# ESP232_USB_C_SCH_1.net
KiCad netlist of a schematic drawn in Altium Designer
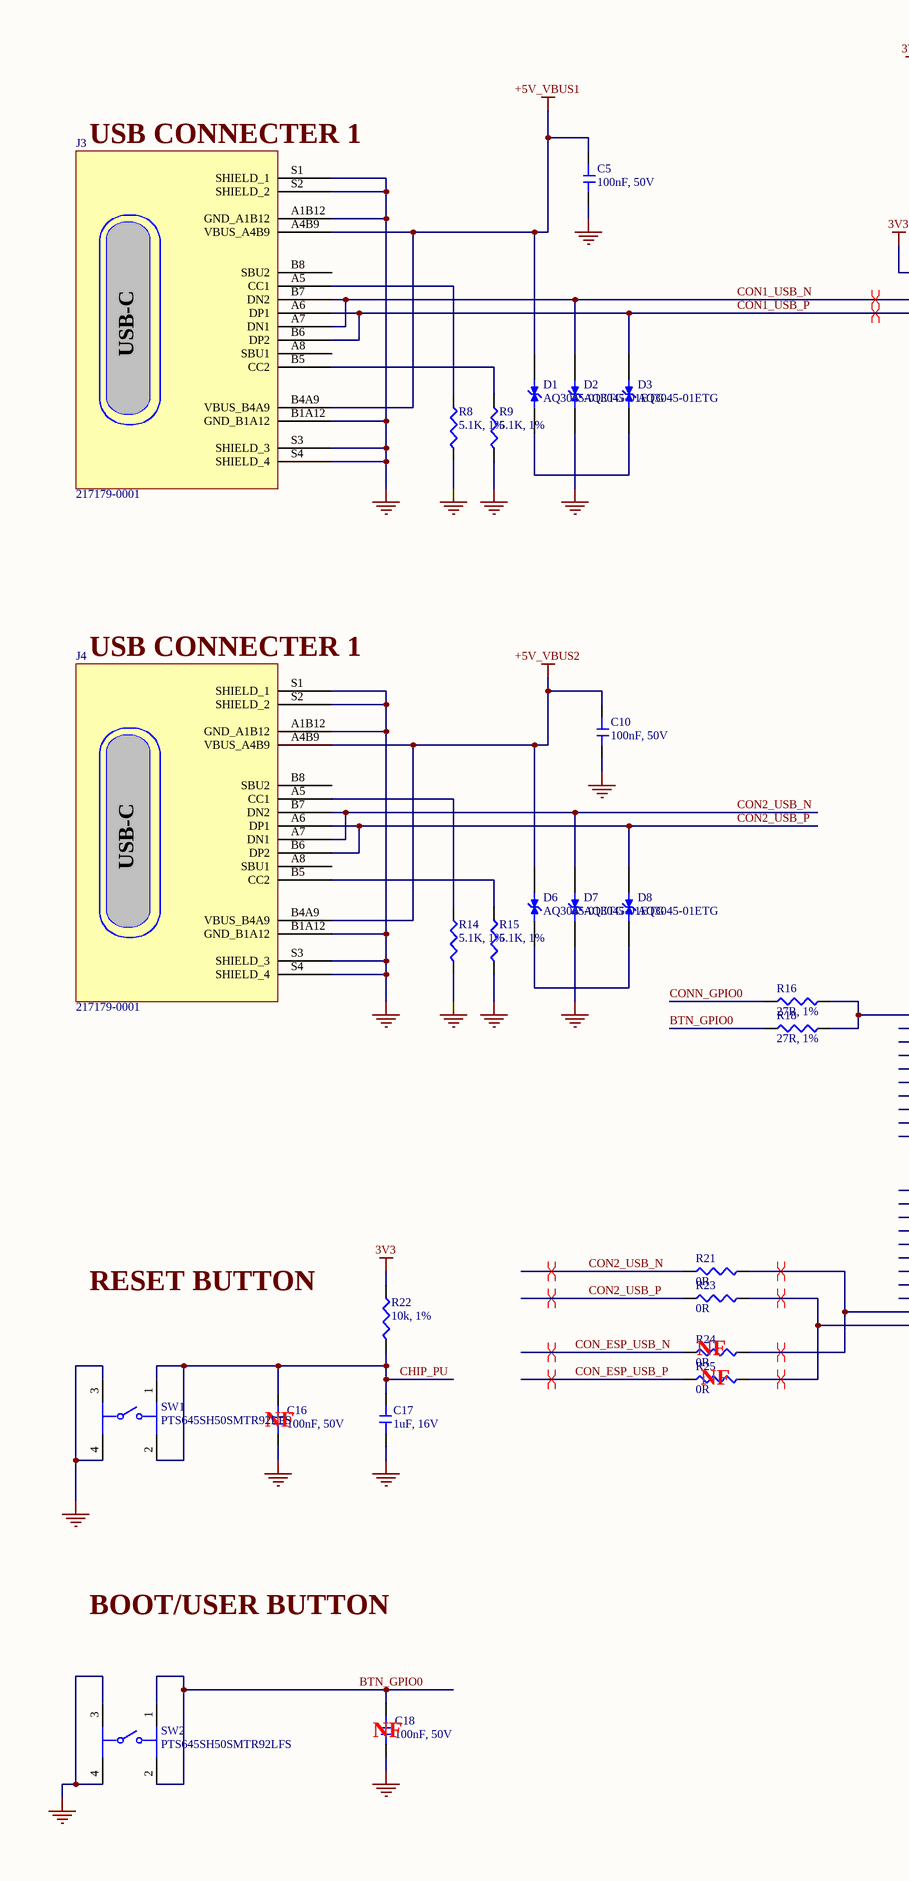
[diagram p0: ESP232_USB_C_SCH_1.SchDoc, left]
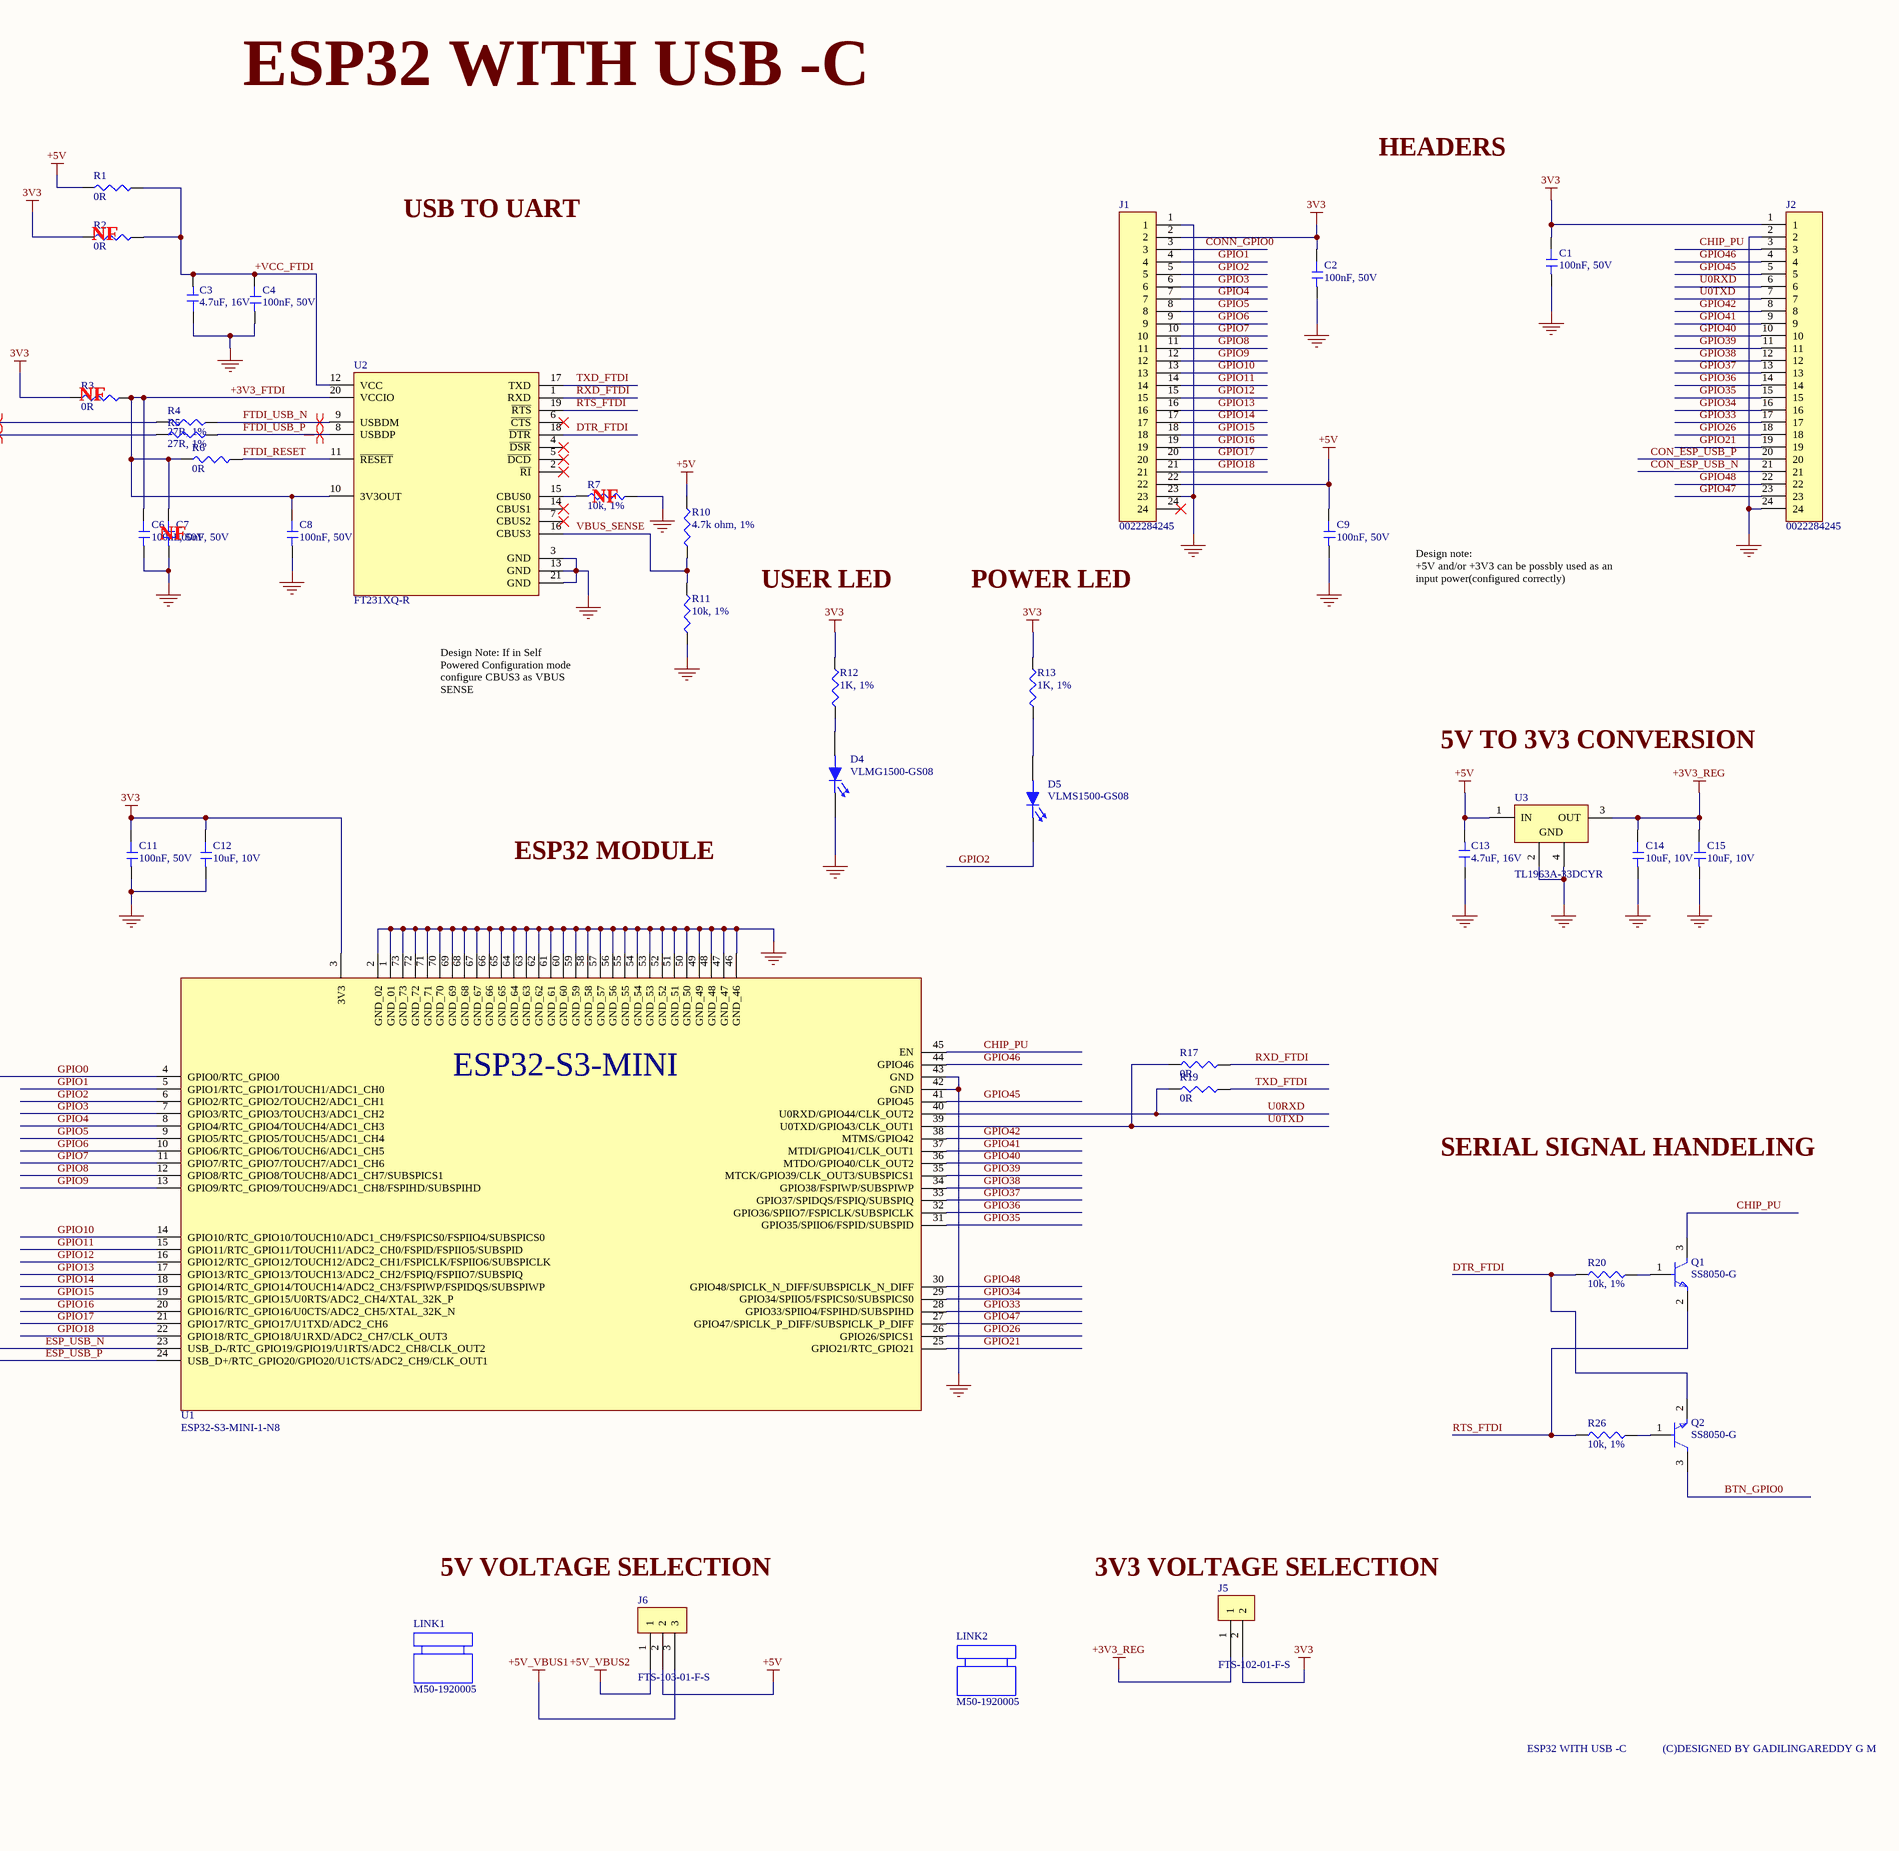
[diagram p1: ESP232_USB_C_SCH_1.SchDoc, right]

(export (version "E")
  (design (tool "Eeschema 10.0.6"))
  (components
    (comp (ref "C1")
      (value "100nF, 50V")
      (footprint "CAPC1005X55N")
      (description "CAP CER 0.1UF 50V X7R 0402")
      (fields
        (field (name "MANUFACTURER") "Samsung")
        (field (name "MANUFACTURER PART NUMBER") "CL05B104KB54PNC")
      )
      (libsource (lib "Schlib1") (part "CL05B104KB54PNC"))
    )
    (comp (ref "C2")
      (value "100nF, 50V")
      (footprint "CAPC1005X55N")
      (description "CAP CER 0.1UF 50V X7R 0402")
      (fields
        (field (name "MANUFACTURER") "Samsung")
        (field (name "MANUFACTURER PART NUMBER") "CL05B104KB54PNC")
      )
      (libsource (lib "Schlib1") (part "CL05B104KB54PNC"))
    )
    (comp (ref "C3")
      (value "4.7uF, 16V")
      (footprint "CAPC1005X55N")
      (description "CAP CER 4.7UF 16V X5R 0402")
      (fields
        (field (name "MANUFACTURER") "Samsung")
        (field (name "MANUFACTURER PART NUMBER") "CL05A475MO5NUNC")
      )
      (libsource (lib "Schlib1") (part "CL05A475MO5NUNC"))
    )
    (comp (ref "C4")
      (value "100nF, 50V")
      (footprint "CAPC1005X55N")
      (description "CAP CER 0.1UF 50V X7R 0402")
      (fields
        (field (name "MANUFACTURER") "Samsung")
        (field (name "MANUFACTURER PART NUMBER") "CL05B104KB54PNC")
      )
      (libsource (lib "Schlib1") (part "CL05B104KB54PNC"))
    )
    (comp (ref "C5")
      (value "100nF, 50V")
      (footprint "CAPC1005X55N")
      (description "CAP CER 0.1UF 50V X7R 0402")
      (fields
        (field (name "MANUFACTURER") "Samsung")
        (field (name "MANUFACTURER PART NUMBER") "CL05B104KB54PNC")
      )
      (libsource (lib "Schlib1") (part "CL05B104KB54PNC"))
    )
    (comp (ref "C6")
      (value "100nF, 50V")
      (footprint "CAPC1005X55N")
      (description "CAP CER 0.1UF 50V X7R 0402")
      (fields
        (field (name "MANUFACTURER") "Samsung")
        (field (name "MANUFACTURER PART NUMBER") "CL05B104KB54PNC")
      )
      (libsource (lib "Schlib1") (part "CL05B104KB54PNC"))
    )
    (comp (ref "C7")
      (value "100nF, 50V")
      (footprint "CAPC1005X55N")
      (description "CAP CER 0.1UF 50V X7R 0402")
      (fields
        (field (name "MANUFACTURER") "Samsung")
        (field (name "MANUFACTURER PART NUMBER") "CL05B104KB54PNC")
      )
      (libsource (lib "Schlib1") (part "CL05B104KB54PNC"))
    )
    (comp (ref "C8")
      (value "100nF, 50V")
      (footprint "CAPC1005X55N")
      (description "CAP CER 0.1UF 50V X7R 0402")
      (fields
        (field (name "MANUFACTURER") "Samsung")
        (field (name "MANUFACTURER PART NUMBER") "CL05B104KB54PNC")
      )
      (libsource (lib "Schlib1") (part "CL05B104KB54PNC"))
    )
    (comp (ref "C9")
      (value "100nF, 50V")
      (footprint "CAPC1005X55N")
      (description "CAP CER 0.1UF 50V X7R 0402")
      (fields
        (field (name "MANUFACTURER") "Samsung")
        (field (name "MANUFACTURER PART NUMBER") "CL05B104KB54PNC")
      )
      (libsource (lib "Schlib1") (part "CL05B104KB54PNC"))
    )
    (comp (ref "C10")
      (value "100nF, 50V")
      (footprint "CAPC1005X55N")
      (description "CAP CER 0.1UF 50V X7R 0402")
      (fields
        (field (name "MANUFACTURER") "Samsung")
        (field (name "MANUFACTURER PART NUMBER") "CL05B104KB54PNC")
      )
      (libsource (lib "Schlib1") (part "CL05B104KB54PNC"))
    )
    (comp (ref "C11")
      (value "100nF, 50V")
      (footprint "CAPC1005X55N")
      (description "CAP CER 0.1UF 50V X7R 0402")
      (fields
        (field (name "MANUFACTURER") "Samsung")
        (field (name "MANUFACTURER PART NUMBER") "CL05B104KB54PNC")
      )
      (libsource (lib "Schlib1") (part "CL05B104KB54PNC"))
    )
    (comp (ref "C12")
      (value "10uF, 10V")
      (footprint "CAPC1005X55N")
      (description "CAP CER 10UF 10V X5R 0402")
      (fields
        (field (name "MANUFACTURER") "Samsung")
        (field (name "MANUFACTURER PART NUMBER") "CL05A106MP8NUB8")
      )
      (libsource (lib "Schlib1") (part "CL05A106MP8NUB8"))
    )
    (comp (ref "C13")
      (value "4.7uF, 16V")
      (footprint "CAPC1005X55N")
      (description "CAP CER 4.7UF 16V X5R 0402")
      (fields
        (field (name "MANUFACTURER") "Samsung")
        (field (name "MANUFACTURER PART NUMBER") "CL05A475MO5NUNC")
      )
      (libsource (lib "Schlib1") (part "CL05A475MO5NUNC"))
    )
    (comp (ref "C14")
      (value "10uF, 10V")
      (footprint "CAPC1005X55N")
      (description "CAP CER 10UF 10V X5R 0402")
      (fields
        (field (name "MANUFACTURER") "Samsung")
        (field (name "MANUFACTURER PART NUMBER") "CL05A106MP8NUB8")
      )
      (libsource (lib "Schlib1") (part "CL05A106MP8NUB8"))
    )
    (comp (ref "C15")
      (value "10uF, 10V")
      (footprint "CAPC1005X55N")
      (description "CAP CER 10UF 10V X5R 0402")
      (fields
        (field (name "MANUFACTURER") "Samsung")
        (field (name "MANUFACTURER PART NUMBER") "CL05A106MP8NUB8")
      )
      (libsource (lib "Schlib1") (part "CL05A106MP8NUB8"))
    )
    (comp (ref "C16")
      (value "100nF, 50V")
      (footprint "CAPC1005X55N")
      (description "CAP CER 0.1UF 50V X7R 0402")
      (fields
        (field (name "MANUFACTURER") "Samsung")
        (field (name "MANUFACTURER PART NUMBER") "CL05B104KB54PNC")
      )
      (libsource (lib "Schlib1") (part "CL05B104KB54PNC"))
    )
    (comp (ref "C17")
      (value "1uF, 16V")
      (footprint "CAPC1005X55N")
      (description "CAP CER 1UF 16V X5R 0402")
      (fields
        (field (name "MANUFACTURER") "Samsung")
        (field (name "MANUFACTURER PART NUMBER") "CL05A105KO5NNNC")
      )
      (libsource (lib "Schlib1") (part "CL05A105KO5NNNC"))
    )
    (comp (ref "C18")
      (value "100nF, 50V")
      (footprint "CAPC1005X55N")
      (description "CAP CER 0.1UF 50V X7R 0402")
      (fields
        (field (name "MANUFACTURER") "Samsung")
        (field (name "MANUFACTURER PART NUMBER") "CL05B104KB54PNC")
      )
      (libsource (lib "Schlib1") (part "CL05B104KB54PNC"))
    )
    (comp (ref "D1")
      (value "AQ3045-01ETG")
      (footprint "ESD_TVS_DIODE")
      (description "TVS DIODE 5.3VWM 12VC SOD882")
      (fields (field (name "MANUFACTURER") "Littelfuse") (field (name "LCSC PART NUMBER") "C3710326"))
      (libsource (lib "Schlib1") (part "AQ3045-01ETG"))
    )
    (comp (ref "D2")
      (value "AQ3045-01ETG")
      (footprint "ESD_TVS_DIODE")
      (description "TVS DIODE 5.3VWM 12VC SOD882")
      (fields (field (name "MANUFACTURER") "Littelfuse") (field (name "LCSC PART NUMBER") "C3710326"))
      (libsource (lib "Schlib1") (part "AQ3045-01ETG"))
    )
    (comp (ref "D3")
      (value "AQ3045-01ETG")
      (footprint "ESD_TVS_DIODE")
      (description "TVS DIODE 5.3VWM 12VC SOD882")
      (fields (field (name "MANUFACTURER") "Littelfuse") (field (name "LCSC PART NUMBER") "C3710326"))
      (libsource (lib "Schlib1") (part "AQ3045-01ETG"))
    )
    (comp (ref "D4")
      (value "VLMG1500-GS08")
      (footprint "GREEN_LED")
      (description "LED YLW-GRN 0402 SMD")
      (fields (field (name "MANUFACTURER") "Vishay") (field (name "LCSC PART NUMBER") "C511404"))
      (libsource (lib "Schlib1") (part "VLMG1500-GS08"))
    )
    (comp (ref "D5")
      (value "VLMS1500-GS08")
      (footprint "RED_LED")
      (description "LED RED 0402 SMD")
      (fields (field (name "MANUFACTURER") "Vishay") (field (name "LCSC PART NUMBER") "C511370"))
      (libsource (lib "Schlib1_1") (part "VLMS1500-GS08"))
    )
    (comp (ref "D6")
      (value "AQ3045-01ETG")
      (footprint "ESD_TVS_DIODE")
      (description "TVS DIODE 5.3VWM 12VC SOD882")
      (fields (field (name "MANUFACTURER") "Littelfuse") (field (name "LCSC PART NUMBER") "C3710326"))
      (libsource (lib "Schlib1") (part "AQ3045-01ETG"))
    )
    (comp (ref "D7")
      (value "AQ3045-01ETG")
      (footprint "ESD_TVS_DIODE")
      (description "TVS DIODE 5.3VWM 12VC SOD882")
      (fields (field (name "MANUFACTURER") "Littelfuse") (field (name "LCSC PART NUMBER") "C3710326"))
      (libsource (lib "Schlib1") (part "AQ3045-01ETG"))
    )
    (comp (ref "D8")
      (value "AQ3045-01ETG")
      (footprint "ESD_TVS_DIODE")
      (description "TVS DIODE 5.3VWM 12VC SOD882")
      (fields (field (name "MANUFACTURER") "Littelfuse") (field (name "LCSC PART NUMBER") "C3710326"))
      (libsource (lib "Schlib1") (part "AQ3045-01ETG"))
    )
    (comp (ref "J1")
      (value "0022284245")
      (footprint "HDR_1X24_2.54MM - duplicate")
      (description "CONN HEADER VERT 24POS 2.54MM")
      (fields (field (name "MANUFACTURER") "Molex") (field (name "LCSC PART NUMBER") "C7145888"))
      (libsource (lib "Schlib1") (part "0022284245"))
    )
    (comp (ref "J2")
      (value "0022284245")
      (footprint "HDR_1X24_2.54MM - duplicate")
      (description "CONN HEADER VERT 24POS 2.54MM")
      (fields (field (name "MANUFACTURER") "Molex") (field (name "LCSC PART NUMBER") "C7145888"))
      (libsource (lib "") (part "0022284245_1"))
    )
    (comp (ref "J3")
      (value "217179-0001")
      (footprint "FP-2171790001-MFG")
      (description "CONN RCP USB2.0 TYP C 24P SMD RA")
      (fields (field (name "MANUFACTURER") "Molex") (field (name "LCSC PART NUMBER") "C2894899"))
      (libsource (lib "Schlib1") (part "217179-0001"))
    )
    (comp (ref "J4")
      (value "217179-0001")
      (footprint "FP-2171790001-MFG")
      (description "CONN RCP USB2.0 TYP C 24P SMD RA")
      (fields (field (name "MANUFACTURER") "Molex") (field (name "LCSC PART NUMBER") "C2894899"))
      (libsource (lib "Schlib1") (part "217179-0001"))
    )
    (comp (ref "J5")
      (value "FTS-102-01-F-S")
      (footprint "HDR_1X2_1.27MM")
      (description "CONN HEADER VERT 2POS 1.27MM")
      (fields (field (name "MANUFACTURER") "Samtec") (field (name "LCSC PART NUMBER") "C6045317"))
      (libsource (lib "Schlib1") (part "FTS-102-01-F-S"))
    )
    (comp (ref "J6")
      (value "FTS-103-01-F-S")
      (footprint "HDR_1X3_1.27MM")
      (description "CONN HEADER VERT 3POS 1.27MM")
      (fields (field (name "MANUFACTURER") "Samtec") (field (name "LCSC PART NUMBER") "C3333578"))
      (libsource (lib "Schlib1") (part "FTS-103-01-F-S"))
    )
    (comp (ref "LINK1")
      (value "M50-1920005")
      (description "CONN SHUNT 1.27MM RED")
      (fields (field (name "MANUFACTURER") "Harwin") (field (name "LCSC PART NUMBER") "C6985646"))
      (libsource (lib "Schlib1") (part "M50-1920005"))
    )
    (comp (ref "LINK2")
      (value "M50-1920005")
      (description "CONN SHUNT 1.27MM RED")
      (fields (field (name "MANUFACTURER") "Harwin") (field (name "LCSC PART NUMBER") "C6985646"))
      (libsource (lib "Schlib1") (part "M50-1920005"))
    )
    (comp (ref "Q1")
      (value "SS8050-G")
      (footprint "FP-SS8050-G-IPC_B")
      (description "TRANS NPN 25V 1.5A SOT23-3")
      (fields (field (name "MANUFACTURER") "Comchip") (field (name "LCSC PART NUMBER") "C164885"))
      (libsource (lib "Schlib1") (part "SS8050-G"))
    )
    (comp (ref "Q2")
      (value "SS8050-G")
      (footprint "FP-SS8050-G-IPC_B")
      (description "TRANS NPN 25V 1.5A SOT23-3")
      (fields (field (name "MANUFACTURER") "Comchip") (field (name "LCSC PART NUMBER") "C164885"))
      (libsource (lib "Schlib1") (part "SS8050-G"))
    )
    (comp (ref "R1")
      (value "0R")
      (footprint "RESC1005X37N")
      (description "RES 0 OHM JUMPER 1/16W 0402")
      (fields
        (field (name "MANUFACTURER") "Yageo")
        (field (name "MANUFACTURER PART NUMBER") "RC0402JR-070RL")
      )
      (libsource (lib "Schlib1") (part "RC0402JR-070RL"))
    )
    (comp (ref "R2")
      (value "0R")
      (footprint "RESC1005X37N")
      (description "RES 0 OHM JUMPER 1/16W 0402")
      (fields
        (field (name "MANUFACTURER") "Yageo")
        (field (name "MANUFACTURER PART NUMBER") "RC0402JR-070RL")
      )
      (libsource (lib "Schlib1") (part "RC0402JR-070RL"))
    )
    (comp (ref "R3")
      (value "0R")
      (footprint "RESC1005X37N")
      (description "RES 0 OHM JUMPER 1/16W 0402")
      (fields
        (field (name "MANUFACTURER") "Yageo")
        (field (name "MANUFACTURER PART NUMBER") "RC0402JR-070RL")
      )
      (libsource (lib "Schlib1") (part "RC0402JR-070RL"))
    )
    (comp (ref "R4")
      (value "27R, 1%")
      (footprint "RESC1005X37N")
      (description "RES 27 OHM 1% 1/16W 0402")
      (fields
        (field (name "MANUFACTURER") "Yageo")
        (field (name "MANUFACTURER PART NUMBER") "RC0402FR-0727RL")
      )
      (libsource (lib "Schlib1") (part "RC0402FR-0727RL"))
    )
    (comp (ref "R5")
      (value "27R, 1%")
      (footprint "RESC1005X37N")
      (description "RES 27 OHM 1% 1/16W 0402")
      (fields
        (field (name "MANUFACTURER") "Yageo")
        (field (name "MANUFACTURER PART NUMBER") "RC0402FR-0727RL")
      )
      (libsource (lib "Schlib1") (part "RC0402FR-0727RL"))
    )
    (comp (ref "R6")
      (value "0R")
      (footprint "RESC1005X37N")
      (description "RES 0 OHM JUMPER 1/16W 0402")
      (fields
        (field (name "MANUFACTURER") "Yageo")
        (field (name "MANUFACTURER PART NUMBER") "RC0402JR-070RL")
      )
      (libsource (lib "Schlib1") (part "RC0402JR-070RL"))
    )
    (comp (ref "R7")
      (value "10k, 1%")
      (footprint "RESC1005X37N")
      (description "RES 10K OHM 1% 1/16W 0402")
      (fields
        (field (name "MANUFACTURER") "Yageo")
        (field (name "MANUFACTURER PART NUMBER") "RC0402FR-0710KL")
      )
      (libsource (lib "Schlib1") (part "RC0402FR-0710KL"))
    )
    (comp (ref "R8")
      (value "5.1K, 1%")
      (footprint "RESC1005X37N")
      (description "RES SMD 5.1K OHM 1% 1/16W 0402")
      (fields
        (field (name "MANUFACTURER") "Yageo")
        (field (name "MANUFACTURER PART NUMBER") "AF0402FR-075K1L")
      )
      (libsource (lib "Schlib1") (part "AF0402FR-075K1L"))
    )
    (comp (ref "R9")
      (value "5.1K, 1%")
      (footprint "RESC1005X37N")
      (description "RES SMD 5.1K OHM 1% 1/16W 0402")
      (fields
        (field (name "MANUFACTURER") "Yageo")
        (field (name "MANUFACTURER PART NUMBER") "AF0402FR-075K1L")
      )
      (libsource (lib "Schlib1") (part "AF0402FR-075K1L"))
    )
    (comp (ref "R10")
      (value "4.7k ohm, 1%")
      (footprint "RESC1005X37N")
      (description "RES 4.7K OHM 1% 1/16W 0402")
      (fields
        (field (name "MANUFACTURER") "Yageo")
        (field (name "MANUFACTURER PART NUMBER") "RC0402FR-074K7L")
      )
      (libsource (lib "Schlib1") (part "RC0402FR-074K7L"))
    )
    (comp (ref "R11")
      (value "10k, 1%")
      (footprint "RESC1005X37N")
      (description "RES 10K OHM 1% 1/16W 0402")
      (fields
        (field (name "MANUFACTURER") "Yageo")
        (field (name "MANUFACTURER PART NUMBER") "RC0402FR-0710KL")
      )
      (libsource (lib "Schlib1") (part "RC0402FR-0710KL"))
    )
    (comp (ref "R12")
      (value "1K, 1%")
      (footprint "RESC1005X37N")
      (description "RES 1K OHM 1% 1/32W 01005")
      (fields
        (field (name "MANUFACTURER") "Yageo")
        (field (name "MANUFACTURER PART NUMBER") "RC0100FR-071KL")
      )
      (libsource (lib "Schlib1") (part "RC0100FR-071KL"))
    )
    (comp (ref "R13")
      (value "1K, 1%")
      (footprint "RESC1005X37N")
      (description "RES 1K OHM 1% 1/32W 01005")
      (fields
        (field (name "MANUFACTURER") "Yageo")
        (field (name "MANUFACTURER PART NUMBER") "RC0100FR-071KL")
      )
      (libsource (lib "Schlib1") (part "RC0100FR-071KL"))
    )
    (comp (ref "R14")
      (value "5.1K, 1%")
      (footprint "RESC1005X37N")
      (description "RES SMD 5.1K OHM 1% 1/16W 0402")
      (fields
        (field (name "MANUFACTURER") "Yageo")
        (field (name "MANUFACTURER PART NUMBER") "AF0402FR-075K1L")
      )
      (libsource (lib "Schlib1") (part "AF0402FR-075K1L"))
    )
    (comp (ref "R15")
      (value "5.1K, 1%")
      (footprint "RESC1005X37N")
      (description "RES SMD 5.1K OHM 1% 1/16W 0402")
      (fields
        (field (name "MANUFACTURER") "Yageo")
        (field (name "MANUFACTURER PART NUMBER") "AF0402FR-075K1L")
      )
      (libsource (lib "Schlib1") (part "AF0402FR-075K1L"))
    )
    (comp (ref "R16")
      (value "27R, 1%")
      (footprint "RESC1005X37N")
      (description "RES 27 OHM 1% 1/16W 0402")
      (fields
        (field (name "MANUFACTURER") "Yageo")
        (field (name "MANUFACTURER PART NUMBER") "RC0402FR-0727RL")
      )
      (libsource (lib "Schlib1") (part "RC0402FR-0727RL"))
    )
    (comp (ref "R17")
      (value "0R")
      (footprint "RESC1005X37N")
      (description "RES 0 OHM JUMPER 1/16W 0402")
      (fields
        (field (name "MANUFACTURER") "Yageo")
        (field (name "MANUFACTURER PART NUMBER") "RC0402JR-070RL")
      )
      (libsource (lib "Schlib1") (part "RC0402JR-070RL"))
    )
    (comp (ref "R18")
      (value "27R, 1%")
      (footprint "RESC1005X37N")
      (description "RES 27 OHM 1% 1/16W 0402")
      (fields
        (field (name "MANUFACTURER") "Yageo")
        (field (name "MANUFACTURER PART NUMBER") "RC0402FR-0727RL")
      )
      (libsource (lib "Schlib1") (part "RC0402FR-0727RL"))
    )
    (comp (ref "R19")
      (value "0R")
      (footprint "RESC1005X37N")
      (description "RES 0 OHM JUMPER 1/16W 0402")
      (fields
        (field (name "MANUFACTURER") "Yageo")
        (field (name "MANUFACTURER PART NUMBER") "RC0402JR-070RL")
      )
      (libsource (lib "Schlib1") (part "RC0402JR-070RL"))
    )
    (comp (ref "R20")
      (value "10k, 1%")
      (footprint "RESC1005X37N")
      (description "RES 10K OHM 1% 1/16W 0402")
      (fields
        (field (name "MANUFACTURER") "Yageo")
        (field (name "MANUFACTURER PART NUMBER") "RC0402FR-0710KL")
      )
      (libsource (lib "Schlib1") (part "RC0402FR-0710KL"))
    )
    (comp (ref "R21")
      (value "0R")
      (footprint "RESC1005X37N")
      (description "RES 0 OHM JUMPER 1/16W 0402")
      (fields
        (field (name "MANUFACTURER") "Yageo")
        (field (name "MANUFACTURER PART NUMBER") "RC0402JR-070RL")
      )
      (libsource (lib "Schlib1") (part "RC0402JR-070RL"))
    )
    (comp (ref "R22")
      (value "10k, 1%")
      (footprint "RESC1005X37N")
      (description "RES 10K OHM 1% 1/16W 0402")
      (fields
        (field (name "MANUFACTURER") "Yageo")
        (field (name "MANUFACTURER PART NUMBER") "RC0402FR-0710KL")
      )
      (libsource (lib "Schlib1") (part "RC0402FR-0710KL"))
    )
    (comp (ref "R23")
      (value "0R")
      (footprint "RESC1005X37N")
      (description "RES 0 OHM JUMPER 1/16W 0402")
      (fields
        (field (name "MANUFACTURER") "Yageo")
        (field (name "MANUFACTURER PART NUMBER") "RC0402JR-070RL")
      )
      (libsource (lib "Schlib1") (part "RC0402JR-070RL"))
    )
    (comp (ref "R24")
      (value "0R")
      (footprint "RESC1005X37N")
      (description "RES 0 OHM JUMPER 1/16W 0402")
      (fields
        (field (name "MANUFACTURER") "Yageo")
        (field (name "MANUFACTURER PART NUMBER") "RC0402JR-070RL")
      )
      (libsource (lib "Schlib1") (part "RC0402JR-070RL"))
    )
    (comp (ref "R25")
      (value "0R")
      (footprint "RESC1005X37N")
      (description "RES 0 OHM JUMPER 1/16W 0402")
      (fields
        (field (name "MANUFACTURER") "Yageo")
        (field (name "MANUFACTURER PART NUMBER") "RC0402JR-070RL")
      )
      (libsource (lib "Schlib1") (part "RC0402JR-070RL"))
    )
    (comp (ref "R26")
      (value "10k, 1%")
      (footprint "RESC1005X37N")
      (description "RES 10K OHM 1% 1/16W 0402")
      (fields
        (field (name "MANUFACTURER") "Yageo")
        (field (name "MANUFACTURER PART NUMBER") "RC0402FR-0710KL")
      )
      (libsource (lib "Schlib1") (part "RC0402FR-0710KL"))
    )
    (comp (ref "SW1")
      (value "PTS645SH50SMTR92LFS")
      (footprint "FP-PTS645SH50SMTR92LFS-MFG")
      (description "SWITCH TACTILE SPST-NO 0.05A 12V")
      (fields (field (name "MANUFACTURER") "ITT C&K") (field (name "LCSC PART NUMBER") "C221869"))
      (libsource (lib "Schlib1") (part "PTS645SH50SMTR92LFS"))
    )
    (comp (ref "SW2")
      (value "PTS645SH50SMTR92LFS")
      (footprint "FP-PTS645SH50SMTR92LFS-MFG")
      (description "SWITCH TACTILE SPST-NO 0.05A 12V")
      (fields (field (name "MANUFACTURER") "ITT C&K") (field (name "LCSC PART NUMBER") "C221869"))
      (libsource (lib "Schlib1") (part "PTS645SH50SMTR92LFS"))
    )
    (comp (ref "U1")
      (value "ESP32-S3-MINI-1-N8")
      (footprint "ESP32-S3-MINI-1-N8")
      (description "SMD module, ESP32-S3FN8, 8 MB SPI flash, PCB antenna")
      (fields (field (name "MANUFACTURER") "Espressif Systems") (field (name "LCSC PART NUMBER") "C2913206"))
      (libsource (lib "Schlib1") (part "ESP32-S3-MINI-1-N8"))
    )
    (comp (ref "U2")
      (value "FT231XQ-R")
      (footprint "FP-QFN-20-IPC_B")
      (description "IC USB SERIAL FULL UART 20QFN")
      (fields (field (name "MANUFACTURER") "FTDI") (field (name "LCSC PART NUMBER") "C132159"))
      (libsource (lib "Schlib1") (part "FT231XQ-R"))
    )
    (comp (ref "U3")
      (value "TL1963A-33DCYR")
      (footprint "DCY0004A_N")
      (description "IC REG LINEAR 3.3V 1.5A SOT223-4")
      (fields (field (name "MANUFACTURER") "Texas Instruments") (field (name "LCSC PART NUMBER") "C181262"))
      (libsource (lib "Schlib1") (part "TL1963A-33DCYR_1"))
    )
  )
  (nets
    (net (code "1") (name "+3V3_REG") (class "Default")
      (node (ref "C14") (pin "2") (pinfunction "2_2") (pintype "passive"))
      (node (ref "C15") (pin "2") (pinfunction "2_2") (pintype "passive"))
      (node (ref "J5") (pin "1") (pinfunction "1_1") (pintype "passive"))
      (node (ref "U3") (pin "3") (pinfunction "OUT_3") (pintype "power_in"))
    )
    (net (code "2") (name "+5V") (class "Default")
      (node (ref "C13") (pin "1") (pinfunction "1_1") (pintype "passive"))
      (node (ref "C9") (pin "2") (pinfunction "2_2") (pintype "passive"))
      (node (ref "J1") (pin "22") (pinfunction "22_22") (pintype "passive"))
      (node (ref "J6") (pin "2") (pinfunction "2_2") (pintype "passive"))
      (node (ref "R1") (pin "1") (pinfunction "1_1") (pintype "passive"))
      (node (ref "R10") (pin "1") (pinfunction "1_1") (pintype "passive"))
      (node (ref "U3") (pin "1") (pinfunction "IN_1") (pintype "power_in"))
    )
    (net (code "3") (name "+5V_VBUS1") (class "Default")
      (node (ref "C5") (pin "2") (pinfunction "2_2") (pintype "passive"))
      (node (ref "D1") (pin "3") (pinfunction "3_3") (pintype "passive"))
      (node (ref "J3") (pin "A4B9") (pinfunction "VBUS_A4B9_A4B9") (pintype "passive"))
      (node (ref "J3") (pin "B4A9") (pinfunction "VBUS_B4A9_B4A9") (pintype "passive"))
      (node (ref "J6") (pin "3") (pinfunction "3_3") (pintype "passive"))
    )
    (net (code "4") (name "+5V_VBUS2") (class "Default")
      (node (ref "C10") (pin "2") (pinfunction "2_2") (pintype "passive"))
      (node (ref "D6") (pin "3") (pinfunction "3_3") (pintype "passive"))
      (node (ref "J4") (pin "A4B9") (pinfunction "VBUS_A4B9_A4B9") (pintype "passive"))
      (node (ref "J4") (pin "B4A9") (pinfunction "VBUS_B4A9_B4A9") (pintype "passive"))
      (node (ref "J6") (pin "1") (pinfunction "1_1") (pintype "passive"))
    )
    (net (code "5") (name "/+3V3_FTDI") (class "Default")
      (node (ref "C6") (pin "2") (pinfunction "2_2") (pintype "passive"))
      (node (ref "C7") (pin "2") (pinfunction "2_2") (pintype "passive"))
      (node (ref "C8") (pin "2") (pinfunction "2_2") (pintype "passive"))
      (node (ref "R3") (pin "2") (pinfunction "2_2") (pintype "passive"))
      (node (ref "R6") (pin "1") (pinfunction "1_1") (pintype "passive"))
      (node (ref "U2") (pin "10") (pinfunction "3V3OUT_10") (pintype "passive"))
      (node (ref "U2") (pin "20") (pinfunction "VCCIO_20") (pintype "passive"))
    )
    (net (code "6") (name "/+VCC_FTDI") (class "Default")
      (node (ref "C3") (pin "1") (pinfunction "1_1") (pintype "passive"))
      (node (ref "C4") (pin "2") (pinfunction "2_2") (pintype "passive"))
      (node (ref "R1") (pin "2") (pinfunction "2_2") (pintype "passive"))
      (node (ref "R2") (pin "2") (pinfunction "2_2") (pintype "passive"))
      (node (ref "U2") (pin "12") (pinfunction "VCC_12") (pintype "passive"))
    )
    (net (code "7") (name "/BTN_GPIO0") (class "Default")
      (node (ref "C18") (pin "2") (pinfunction "2_2") (pintype "passive"))
      (node (ref "Q2") (pin "3") (pinfunction "C_3") (pintype "passive"))
      (node (ref "R18") (pin "1") (pinfunction "1_1") (pintype "passive"))
      (node (ref "SW2") (pin "1") (pinfunction "1_1") (pintype "passive"))
      (node (ref "SW2") (pin "2") (pinfunction "2_2") (pintype "passive"))
    )
    (net (code "8") (name "/CHIP_PU") (class "Default")
      (node (ref "C16") (pin "2") (pinfunction "2_2") (pintype "passive"))
      (node (ref "C17") (pin "1") (pinfunction "1_1") (pintype "passive"))
      (node (ref "J2") (pin "3") (pinfunction "3_3") (pintype "passive"))
      (node (ref "Q1") (pin "3") (pinfunction "C_3") (pintype "passive"))
      (node (ref "R22") (pin "1") (pinfunction "1_1") (pintype "passive"))
      (node (ref "SW1") (pin "1") (pinfunction "1_1") (pintype "passive"))
      (node (ref "SW1") (pin "2") (pinfunction "2_2") (pintype "passive"))
      (node (ref "U1") (pin "45") (pinfunction "EN_45") (pintype "passive"))
    )
    (net (code "9") (name "/CON1_USB_N") (class "Default")
      (node (ref "D2") (pin "3") (pinfunction "3_3") (pintype "passive"))
      (node (ref "J3") (pin "A7") (pinfunction "DN1_A7") (pintype "passive"))
      (node (ref "J3") (pin "B7") (pinfunction "DN2_B7") (pintype "passive"))
      (node (ref "R4") (pin "1") (pinfunction "1_1") (pintype "passive"))
    )
    (net (code "10") (name "/CON1_USB_P") (class "Default")
      (node (ref "D3") (pin "3") (pinfunction "3_3") (pintype "passive"))
      (node (ref "J3") (pin "A6") (pinfunction "DP1_A6") (pintype "passive"))
      (node (ref "J3") (pin "B6") (pinfunction "DP2_B6") (pintype "passive"))
      (node (ref "R5") (pin "1") (pinfunction "1_1") (pintype "passive"))
    )
    (net (code "11") (name "/CON2_USB_N") (class "Default")
      (node (ref "D7") (pin "3") (pinfunction "3_3") (pintype "passive"))
      (node (ref "J4") (pin "A7") (pinfunction "DN1_A7") (pintype "passive"))
      (node (ref "J4") (pin "B7") (pinfunction "DN2_B7") (pintype "passive"))
      (node (ref "R21") (pin "1") (pinfunction "1_1") (pintype "passive"))
    )
    (net (code "12") (name "/CON2_USB_P") (class "Default")
      (node (ref "D8") (pin "3") (pinfunction "3_3") (pintype "passive"))
      (node (ref "J4") (pin "A6") (pinfunction "DP1_A6") (pintype "passive"))
      (node (ref "J4") (pin "B6") (pinfunction "DP2_B6") (pintype "passive"))
      (node (ref "R23") (pin "1") (pinfunction "1_1") (pintype "passive"))
    )
    (net (code "13") (name "/CONN_GPIO0") (class "Default")
      (node (ref "J1") (pin "3") (pinfunction "3_3") (pintype "passive"))
      (node (ref "R16") (pin "1") (pinfunction "1_1") (pintype "passive"))
    )
    (net (code "14") (name "/CON_ESP_USB_N") (class "Default")
      (node (ref "J2") (pin "21") (pinfunction "21_21") (pintype "passive"))
      (node (ref "R24") (pin "1") (pinfunction "1_1") (pintype "passive"))
    )
    (net (code "15") (name "/CON_ESP_USB_P") (class "Default")
      (node (ref "J2") (pin "20") (pinfunction "20_20") (pintype "passive"))
      (node (ref "R25") (pin "1") (pinfunction "1_1") (pintype "passive"))
    )
    (net (code "16") (name "/DTR_FTDI") (class "Default")
      (node (ref "Q2") (pin "2") (pinfunction "E_2") (pintype "passive"))
      (node (ref "R20") (pin "1") (pinfunction "1_1") (pintype "passive"))
      (node (ref "U2") (pin "18") (pinfunction "~{DTR}_18") (pintype "passive"))
    )
    (net (code "17") (name "/ESP_USB_N") (class "Default")
      (node (ref "R21") (pin "2") (pinfunction "2_2") (pintype "passive"))
      (node (ref "R24") (pin "2") (pinfunction "2_2") (pintype "passive"))
      (node (ref "U1") (pin "23") (pinfunction "USB_D-/RTC_GPIO19/GPIO19/U1RTS/ADC2_CH8/CLK_OUT2_23") (pintype "passive"))
    )
    (net (code "18") (name "/ESP_USB_P") (class "Default")
      (node (ref "R23") (pin "2") (pinfunction "2_2") (pintype "passive"))
      (node (ref "R25") (pin "2") (pinfunction "2_2") (pintype "passive"))
      (node (ref "U1") (pin "24") (pinfunction "USB_D+/RTC_GPIO20/GPIO20/U1CTS/ADC2_CH9/CLK_OUT1_24") (pintype "passive"))
    )
    (net (code "19") (name "/FTDI_RESET") (class "Default")
      (node (ref "R6") (pin "2") (pinfunction "2_2") (pintype "passive"))
      (node (ref "U2") (pin "11") (pinfunction "~{RESET}_11") (pintype "passive"))
    )
    (net (code "20") (name "/FTDI_USB_N") (class "Default")
      (node (ref "R4") (pin "2") (pinfunction "2_2") (pintype "passive"))
      (node (ref "U2") (pin "9") (pinfunction "USBDM_9") (pintype "passive"))
    )
    (net (code "21") (name "/FTDI_USB_P") (class "Default")
      (node (ref "R5") (pin "2") (pinfunction "2_2") (pintype "passive"))
      (node (ref "U2") (pin "8") (pinfunction "USBDP_8") (pintype "passive"))
    )
    (net (code "22") (name "/GPIO0") (class "Default")
      (node (ref "R16") (pin "2") (pinfunction "2_2") (pintype "passive"))
      (node (ref "R18") (pin "2") (pinfunction "2_2") (pintype "passive"))
      (node (ref "U1") (pin "4") (pinfunction "GPIO0/RTC_GPIO0_4") (pintype "passive"))
    )
    (net (code "23") (name "/GPIO1") (class "Default")
      (node (ref "J1") (pin "4") (pinfunction "4_4") (pintype "passive"))
      (node (ref "U1") (pin "5") (pinfunction "GPIO1/RTC_GPIO1/TOUCH1/ADC1_CH0_5") (pintype "passive"))
    )
    (net (code "24") (name "/GPIO2") (class "Default")
      (node (ref "D5") (pin "26") (pinfunction "26_26") (pintype "passive"))
      (node (ref "J1") (pin "5") (pinfunction "5_5") (pintype "passive"))
      (node (ref "U1") (pin "6") (pinfunction "GPIO2/RTC_GPIO2/TOUCH2/ADC1_CH1_6") (pintype "passive"))
    )
    (net (code "25") (name "/GPIO3") (class "Default")
      (node (ref "J1") (pin "6") (pinfunction "6_6") (pintype "passive"))
      (node (ref "U1") (pin "7") (pinfunction "GPIO3/RTC_GPIO3/TOUCH3/ADC1_CH2_7") (pintype "passive"))
    )
    (net (code "26") (name "/GPIO4") (class "Default")
      (node (ref "J1") (pin "7") (pinfunction "7_7") (pintype "passive"))
      (node (ref "U1") (pin "8") (pinfunction "GPIO4/RTC_GPIO4/TOUCH4/ADC1_CH3_8") (pintype "passive"))
    )
    (net (code "27") (name "/GPIO5") (class "Default")
      (node (ref "J1") (pin "8") (pinfunction "8_8") (pintype "passive"))
      (node (ref "U1") (pin "9") (pinfunction "GPIO5/RTC_GPIO5/TOUCH5/ADC1_CH4_9") (pintype "passive"))
    )
    (net (code "28") (name "/GPIO6") (class "Default")
      (node (ref "J1") (pin "9") (pinfunction "9_9") (pintype "passive"))
      (node (ref "U1") (pin "10") (pinfunction "GPIO6/RTC_GPIO6/TOUCH6/ADC1_CH5_10") (pintype "passive"))
    )
    (net (code "29") (name "/GPIO7") (class "Default")
      (node (ref "J1") (pin "10") (pinfunction "10_10") (pintype "passive"))
      (node (ref "U1") (pin "11") (pinfunction "GPIO7/RTC_GPIO7/TOUCH7/ADC1_CH6_11") (pintype "passive"))
    )
    (net (code "30") (name "/GPIO8") (class "Default")
      (node (ref "J1") (pin "11") (pinfunction "11_11") (pintype "passive"))
      (node (ref "U1") (pin "12") (pinfunction "GPIO8/RTC_GPIO8/TOUCH8/ADC1_CH7/SUBSPICS1_12") (pintype "passive"))
    )
    (net (code "31") (name "/GPIO9") (class "Default")
      (node (ref "J1") (pin "12") (pinfunction "12_12") (pintype "passive"))
      (node (ref "U1") (pin "13") (pinfunction "GPIO9/RTC_GPIO9/TOUCH9/ADC1_CH8/FSPIHD/SUBSPIHD_13") (pintype "passive"))
    )
    (net (code "32") (name "/GPIO10") (class "Default")
      (node (ref "J1") (pin "13") (pinfunction "13_13") (pintype "passive"))
      (node (ref "U1") (pin "14") (pinfunction "GPIO10/RTC_GPIO10/TOUCH10/ADC1_CH9/FSPICS0/FSPIIO4/SUBSPICS0_14") (pintype "passive"))
    )
    (net (code "33") (name "/GPIO11") (class "Default")
      (node (ref "J1") (pin "14") (pinfunction "14_14") (pintype "passive"))
      (node (ref "U1") (pin "15") (pinfunction "GPIO11/RTC_GPIO11/TOUCH11/ADC2_CH0/FSPID/FSPIIO5/SUBSPID_15") (pintype "passive"))
    )
    (net (code "34") (name "/GPIO12") (class "Default")
      (node (ref "J1") (pin "15") (pinfunction "15_15") (pintype "passive"))
      (node (ref "U1") (pin "16") (pinfunction "GPIO12/RTC_GPIO12/TOUCH12/ADC2_CH1/FSPICLK/FSPIIO6/SUBSPICLK_16") (pintype "passive"))
    )
    (net (code "35") (name "/GPIO13") (class "Default")
      (node (ref "J1") (pin "16") (pinfunction "16_16") (pintype "passive"))
      (node (ref "U1") (pin "17") (pinfunction "GPIO13/RTC_GPIO13/TOUCH13/ADC2_CH2/FSPIQ/FSPIIO7/SUBSPIQ_17") (pintype "passive"))
    )
    (net (code "36") (name "/GPIO14") (class "Default")
      (node (ref "J1") (pin "17") (pinfunction "17_17") (pintype "passive"))
      (node (ref "U1") (pin "18") (pinfunction "GPIO14/RTC_GPIO14/TOUCH14/ADC2_CH3/FSPIWP/FSPIDQS/SUBSPIWP_18") (pintype "passive"))
    )
    (net (code "37") (name "/GPIO15") (class "Default")
      (node (ref "J1") (pin "18") (pinfunction "18_18") (pintype "passive"))
      (node (ref "U1") (pin "19") (pinfunction "GPIO15/RTC_GPIO15/U0RTS/ADC2_CH4/XTAL_32K_P_19") (pintype "passive"))
    )
    (net (code "38") (name "/GPIO16") (class "Default")
      (node (ref "J1") (pin "19") (pinfunction "19_19") (pintype "passive"))
      (node (ref "U1") (pin "20") (pinfunction "GPIO16/RTC_GPIO16/U0CTS/ADC2_CH5/XTAL_32K_N_20") (pintype "passive"))
    )
    (net (code "39") (name "/GPIO17") (class "Default")
      (node (ref "J1") (pin "20") (pinfunction "20_20") (pintype "passive"))
      (node (ref "U1") (pin "21") (pinfunction "GPIO17/RTC_GPIO17/U1TXD/ADC2_CH6_21") (pintype "passive"))
    )
    (net (code "40") (name "/GPIO18") (class "Default")
      (node (ref "J1") (pin "21") (pinfunction "21_21") (pintype "passive"))
      (node (ref "U1") (pin "22") (pinfunction "GPIO18/RTC_GPIO18/U1RXD/ADC2_CH7/CLK_OUT3_22") (pintype "passive"))
    )
    (net (code "41") (name "/GPIO21") (class "Default")
      (node (ref "J2") (pin "19") (pinfunction "19_19") (pintype "passive"))
      (node (ref "U1") (pin "25") (pinfunction "GPIO21/RTC_GPIO21_25") (pintype "passive"))
    )
    (net (code "42") (name "/GPIO26") (class "Default")
      (node (ref "J2") (pin "18") (pinfunction "18_18") (pintype "passive"))
      (node (ref "U1") (pin "26") (pinfunction "GPIO26/SPICS1_26") (pintype "passive"))
    )
    (net (code "43") (name "/GPIO33") (class "Default")
      (node (ref "J2") (pin "17") (pinfunction "17_17") (pintype "passive"))
      (node (ref "U1") (pin "28") (pinfunction "GPIO33/SPIIO4/FSPIHD/SUBSPIHD_28") (pintype "passive"))
    )
    (net (code "44") (name "/GPIO34") (class "Default")
      (node (ref "J2") (pin "16") (pinfunction "16_16") (pintype "passive"))
      (node (ref "U1") (pin "29") (pinfunction "GPIO34/SPIIO5/FSPICS0/SUBSPICS0_29") (pintype "passive"))
    )
    (net (code "45") (name "/GPIO35") (class "Default")
      (node (ref "J2") (pin "15") (pinfunction "15_15") (pintype "passive"))
      (node (ref "U1") (pin "31") (pinfunction "GPIO35/SPIIO6/FSPID/SUBSPID_31") (pintype "passive"))
    )
    (net (code "46") (name "/GPIO36") (class "Default")
      (node (ref "J2") (pin "14") (pinfunction "14_14") (pintype "passive"))
      (node (ref "U1") (pin "32") (pinfunction "GPIO36/SPIIO7/FSPICLK/SUBSPICLK_32") (pintype "passive"))
    )
    (net (code "47") (name "/GPIO37") (class "Default")
      (node (ref "J2") (pin "13") (pinfunction "13_13") (pintype "passive"))
      (node (ref "U1") (pin "33") (pinfunction "GPIO37/SPIDQS/FSPIQ/SUBSPIQ_33") (pintype "passive"))
    )
    (net (code "48") (name "/GPIO38") (class "Default")
      (node (ref "J2") (pin "12") (pinfunction "12_12") (pintype "passive"))
      (node (ref "U1") (pin "34") (pinfunction "GPIO38/FSPIWP/SUBSPIWP_34") (pintype "passive"))
    )
    (net (code "49") (name "/GPIO39") (class "Default")
      (node (ref "J2") (pin "11") (pinfunction "11_11") (pintype "passive"))
      (node (ref "U1") (pin "35") (pinfunction "MTCK/GPIO39/CLK_OUT3/SUBSPICS1_35") (pintype "passive"))
    )
    (net (code "50") (name "/GPIO40") (class "Default")
      (node (ref "J2") (pin "10") (pinfunction "10_10") (pintype "passive"))
      (node (ref "U1") (pin "36") (pinfunction "MTDO/GPIO40/CLK_OUT2_36") (pintype "passive"))
    )
    (net (code "51") (name "/GPIO41") (class "Default")
      (node (ref "J2") (pin "9") (pinfunction "9_9") (pintype "passive"))
      (node (ref "U1") (pin "37") (pinfunction "MTDI/GPIO41/CLK_OUT1_37") (pintype "passive"))
    )
    (net (code "52") (name "/GPIO42") (class "Default")
      (node (ref "J2") (pin "8") (pinfunction "8_8") (pintype "passive"))
      (node (ref "U1") (pin "38") (pinfunction "MTMS/GPIO42_38") (pintype "passive"))
    )
    (net (code "53") (name "/GPIO45") (class "Default")
      (node (ref "J2") (pin "5") (pinfunction "5_5") (pintype "passive"))
      (node (ref "U1") (pin "41") (pinfunction "GPIO45_41") (pintype "passive"))
    )
    (net (code "54") (name "/GPIO46") (class "Default")
      (node (ref "J2") (pin "4") (pinfunction "4_4") (pintype "passive"))
      (node (ref "U1") (pin "44") (pinfunction "GPIO46_44") (pintype "passive"))
    )
    (net (code "55") (name "/GPIO47") (class "Default")
      (node (ref "J2") (pin "23") (pinfunction "23_23") (pintype "passive"))
      (node (ref "U1") (pin "27") (pinfunction "GPIO47/SPICLK_P_DIFF/SUBSPICLK_P_DIFF_27") (pintype "passive"))
    )
    (net (code "56") (name "/GPIO48") (class "Default")
      (node (ref "J2") (pin "22") (pinfunction "22_22") (pintype "passive"))
      (node (ref "U1") (pin "30") (pinfunction "GPIO48/SPICLK_N_DIFF/SUBSPICLK_N_DIFF_30") (pintype "passive"))
    )
    (net (code "57") (name "/RTS_FTDI") (class "Default")
      (node (ref "Q1") (pin "2") (pinfunction "E_2") (pintype "passive"))
      (node (ref "R26") (pin "1") (pinfunction "1_1") (pintype "passive"))
      (node (ref "U2") (pin "19") (pinfunction "~{RTS}_19") (pintype "passive"))
    )
    (net (code "58") (name "/RXD_FTDI") (class "Default")
      (node (ref "R17") (pin "2") (pinfunction "2_2") (pintype "passive"))
      (node (ref "U2") (pin "1") (pinfunction "RXD_1") (pintype "passive"))
    )
    (net (code "59") (name "/TXD_FTDI") (class "Default")
      (node (ref "R19") (pin "2") (pinfunction "2_2") (pintype "passive"))
      (node (ref "U2") (pin "17") (pinfunction "TXD_17") (pintype "passive"))
    )
    (net (code "60") (name "/U0RXD") (class "Default")
      (node (ref "J2") (pin "6") (pinfunction "6_6") (pintype "passive"))
      (node (ref "R19") (pin "1") (pinfunction "1_1") (pintype "passive"))
      (node (ref "U1") (pin "40") (pinfunction "U0RXD/GPIO44/CLK_OUT2_40") (pintype "passive"))
    )
    (net (code "61") (name "/U0TXD") (class "Default")
      (node (ref "J2") (pin "7") (pinfunction "7_7") (pintype "passive"))
      (node (ref "R17") (pin "1") (pinfunction "1_1") (pintype "passive"))
      (node (ref "U1") (pin "39") (pinfunction "U0TXD/GPIO43/CLK_OUT1_39") (pintype "passive"))
    )
    (net (code "62") (name "/VBUS_SENSE") (class "Default")
      (node (ref "R10") (pin "2") (pinfunction "2_2") (pintype "passive"))
      (node (ref "R11") (pin "1") (pinfunction "1_1") (pintype "passive"))
      (node (ref "U2") (pin "16") (pinfunction "CBUS3_16") (pintype "passive"))
    )
    (net (code "63") (name "3V3") (class "Default")
      (node (ref "C1") (pin "2") (pinfunction "2_2") (pintype "passive"))
      (node (ref "C11") (pin "2") (pinfunction "2_2") (pintype "passive"))
      (node (ref "C12") (pin "2") (pinfunction "2_2") (pintype "passive"))
      (node (ref "C2") (pin "2") (pinfunction "2_2") (pintype "passive"))
      (node (ref "J1") (pin "2") (pinfunction "2_2") (pintype "passive"))
      (node (ref "J2") (pin "1") (pinfunction "1_1") (pintype "passive"))
      (node (ref "J5") (pin "2") (pinfunction "2_2") (pintype "passive"))
      (node (ref "R12") (pin "1") (pinfunction "1_1") (pintype "passive"))
      (node (ref "R13") (pin "1") (pinfunction "1_1") (pintype "passive"))
      (node (ref "R2") (pin "1") (pinfunction "1_1") (pintype "passive"))
      (node (ref "R22") (pin "2") (pinfunction "2_2") (pintype "passive"))
      (node (ref "R3") (pin "1") (pinfunction "1_1") (pintype "passive"))
      (node (ref "U1") (pin "3") (pinfunction "3V3_3") (pintype "passive"))
    )
    (net (code "64") (name "GND") (class "Default")
      (node (ref "C1") (pin "1") (pinfunction "1_1") (pintype "passive"))
      (node (ref "C10") (pin "1") (pinfunction "1_1") (pintype "passive"))
      (node (ref "C11") (pin "1") (pinfunction "1_1") (pintype "passive"))
      (node (ref "C12") (pin "1") (pinfunction "1_1") (pintype "passive"))
      (node (ref "C13") (pin "2") (pinfunction "2_2") (pintype "passive"))
      (node (ref "C14") (pin "1") (pinfunction "1_1") (pintype "passive"))
      (node (ref "C15") (pin "1") (pinfunction "1_1") (pintype "passive"))
      (node (ref "C16") (pin "1") (pinfunction "1_1") (pintype "passive"))
      (node (ref "C17") (pin "2") (pinfunction "2_2") (pintype "passive"))
      (node (ref "C18") (pin "1") (pinfunction "1_1") (pintype "passive"))
      (node (ref "C2") (pin "1") (pinfunction "1_1") (pintype "passive"))
      (node (ref "C3") (pin "2") (pinfunction "2_2") (pintype "passive"))
      (node (ref "C4") (pin "1") (pinfunction "1_1") (pintype "passive"))
      (node (ref "C5") (pin "1") (pinfunction "1_1") (pintype "passive"))
      (node (ref "C6") (pin "1") (pinfunction "1_1") (pintype "passive"))
      (node (ref "C7") (pin "1") (pinfunction "1_1") (pintype "passive"))
      (node (ref "C8") (pin "1") (pinfunction "1_1") (pintype "passive"))
      (node (ref "C9") (pin "1") (pinfunction "1_1") (pintype "passive"))
      (node (ref "D2") (pin "4") (pinfunction "4_4") (pintype "passive"))
      (node (ref "D4") (pin "26") (pinfunction "26_26") (pintype "passive"))
      (node (ref "D7") (pin "4") (pinfunction "4_4") (pintype "passive"))
      (node (ref "J1") (pin "1") (pinfunction "1_1") (pintype "passive"))
      (node (ref "J1") (pin "23") (pinfunction "23_23") (pintype "passive"))
      (node (ref "J2") (pin "2") (pinfunction "2_2") (pintype "passive"))
      (node (ref "J2") (pin "24") (pinfunction "24_24") (pintype "passive"))
      (node (ref "J3") (pin "A1B12") (pinfunction "GND_A1B12_A1B12") (pintype "passive"))
      (node (ref "J3") (pin "B1A12") (pinfunction "GND_B1A12_B1A12") (pintype "passive"))
      (node (ref "J3") (pin "S1") (pinfunction "SHIELD_1_S1") (pintype "passive"))
      (node (ref "J3") (pin "S2") (pinfunction "SHIELD_2_S2") (pintype "passive"))
      (node (ref "J3") (pin "S3") (pinfunction "SHIELD_3_S3") (pintype "passive"))
      (node (ref "J3") (pin "S4") (pinfunction "SHIELD_4_S4") (pintype "passive"))
      (node (ref "J4") (pin "A1B12") (pinfunction "GND_A1B12_A1B12") (pintype "passive"))
      (node (ref "J4") (pin "B1A12") (pinfunction "GND_B1A12_B1A12") (pintype "passive"))
      (node (ref "J4") (pin "S1") (pinfunction "SHIELD_1_S1") (pintype "passive"))
      (node (ref "J4") (pin "S2") (pinfunction "SHIELD_2_S2") (pintype "passive"))
      (node (ref "J4") (pin "S3") (pinfunction "SHIELD_3_S3") (pintype "passive"))
      (node (ref "J4") (pin "S4") (pinfunction "SHIELD_4_S4") (pintype "passive"))
      (node (ref "R11") (pin "2") (pinfunction "2_2") (pintype "passive"))
      (node (ref "R14") (pin "2") (pinfunction "2_2") (pintype "passive"))
      (node (ref "R15") (pin "2") (pinfunction "2_2") (pintype "passive"))
      (node (ref "R7") (pin "2") (pinfunction "2_2") (pintype "passive"))
      (node (ref "R8") (pin "2") (pinfunction "2_2") (pintype "passive"))
      (node (ref "R9") (pin "2") (pinfunction "2_2") (pintype "passive"))
      (node (ref "SW1") (pin "3") (pinfunction "3_3") (pintype "passive"))
      (node (ref "SW1") (pin "4") (pinfunction "4_4") (pintype "passive"))
      (node (ref "SW2") (pin "3") (pinfunction "3_3") (pintype "passive"))
      (node (ref "SW2") (pin "4") (pinfunction "4_4") (pintype "passive"))
      (node (ref "U1") (pin "1") (pinfunction "GND_01_1") (pintype "passive"))
      (node (ref "U1") (pin "2") (pinfunction "GND_02_2") (pintype "passive"))
      (node (ref "U1") (pin "42") (pinfunction "GND_42") (pintype "passive"))
      (node (ref "U1") (pin "43") (pinfunction "GND_43") (pintype "passive"))
      (node (ref "U1") (pin "46") (pinfunction "GND_46_46") (pintype "passive"))
      (node (ref "U1") (pin "47") (pinfunction "GND_47_47") (pintype "passive"))
      (node (ref "U1") (pin "48") (pinfunction "GND_48_48") (pintype "passive"))
      (node (ref "U1") (pin "49") (pinfunction "GND_49_49") (pintype "passive"))
      (node (ref "U1") (pin "50") (pinfunction "GND_50_50") (pintype "passive"))
      (node (ref "U1") (pin "51") (pinfunction "GND_51_51") (pintype "passive"))
      (node (ref "U1") (pin "52") (pinfunction "GND_52_52") (pintype "passive"))
      (node (ref "U1") (pin "53") (pinfunction "GND_53_53") (pintype "passive"))
      (node (ref "U1") (pin "54") (pinfunction "GND_54_54") (pintype "passive"))
      (node (ref "U1") (pin "55") (pinfunction "GND_55_55") (pintype "passive"))
      (node (ref "U1") (pin "56") (pinfunction "GND_56_56") (pintype "passive"))
      (node (ref "U1") (pin "57") (pinfunction "GND_57_57") (pintype "passive"))
      (node (ref "U1") (pin "58") (pinfunction "GND_58_58") (pintype "passive"))
      (node (ref "U1") (pin "59") (pinfunction "GND_59_59") (pintype "passive"))
      (node (ref "U1") (pin "60") (pinfunction "GND_60_60") (pintype "passive"))
      (node (ref "U1") (pin "61") (pinfunction "GND_61_61") (pintype "passive"))
      (node (ref "U1") (pin "62") (pinfunction "GND_62_62") (pintype "passive"))
      (node (ref "U1") (pin "63") (pinfunction "GND_63_63") (pintype "passive"))
      (node (ref "U1") (pin "64") (pinfunction "GND_64_64") (pintype "passive"))
      (node (ref "U1") (pin "65") (pinfunction "GND_65_65") (pintype "passive"))
      (node (ref "U1") (pin "66") (pinfunction "GND_66_66") (pintype "passive"))
      (node (ref "U1") (pin "67") (pinfunction "GND_67_67") (pintype "passive"))
      (node (ref "U1") (pin "68") (pinfunction "GND_68_68") (pintype "passive"))
      (node (ref "U1") (pin "69") (pinfunction "GND_69_69") (pintype "passive"))
      (node (ref "U1") (pin "70") (pinfunction "GND_70_70") (pintype "passive"))
      (node (ref "U1") (pin "71") (pinfunction "GND_71_71") (pintype "passive"))
      (node (ref "U1") (pin "72") (pinfunction "GND_72_72") (pintype "passive"))
      (node (ref "U1") (pin "73") (pinfunction "GND_73_73") (pintype "passive"))
      (node (ref "U2") (pin "13") (pinfunction "GND_13") (pintype "passive"))
      (node (ref "U2") (pin "21") (pinfunction "GND_21") (pintype "passive"))
      (node (ref "U2") (pin "3") (pinfunction "GND_3") (pintype "passive"))
      (node (ref "U3") (pin "2") (pinfunction "GND_2") (pintype "power_in"))
      (node (ref "U3") (pin "4") (pinfunction "GND_4") (pintype "power_in"))
    )
    (net (code "65") (name "Net-(D1-Pad4)") (class "Default")
      (node (ref "D1") (pin "4") (pinfunction "4_4") (pintype "passive"))
      (node (ref "D3") (pin "4") (pinfunction "4_4") (pintype "passive"))
    )
    (net (code "66") (name "Net-(D4-Pad25)") (class "Default")
      (node (ref "D4") (pin "25") (pinfunction "25_25") (pintype "passive"))
      (node (ref "R12") (pin "2") (pinfunction "2_2") (pintype "passive"))
    )
    (net (code "67") (name "Net-(D5-Pad25)") (class "Default")
      (node (ref "D5") (pin "25") (pinfunction "25_25") (pintype "passive"))
      (node (ref "R13") (pin "2") (pinfunction "2_2") (pintype "passive"))
    )
    (net (code "68") (name "Net-(D6-Pad4)") (class "Default")
      (node (ref "D6") (pin "4") (pinfunction "4_4") (pintype "passive"))
      (node (ref "D8") (pin "4") (pinfunction "4_4") (pintype "passive"))
    )
    (net (code "69") (name "Net-(J3-CC1)") (class "Default")
      (node (ref "J3") (pin "A5") (pinfunction "CC1_A5") (pintype "passive"))
      (node (ref "R8") (pin "1") (pinfunction "1_1") (pintype "passive"))
    )
    (net (code "70") (name "Net-(J3-CC2)") (class "Default")
      (node (ref "J3") (pin "B5") (pinfunction "CC2_B5") (pintype "passive"))
      (node (ref "R9") (pin "1") (pinfunction "1_1") (pintype "passive"))
    )
    (net (code "71") (name "Net-(J4-CC1)") (class "Default")
      (node (ref "J4") (pin "A5") (pinfunction "CC1_A5") (pintype "passive"))
      (node (ref "R14") (pin "1") (pinfunction "1_1") (pintype "passive"))
    )
    (net (code "72") (name "Net-(J4-CC2)") (class "Default")
      (node (ref "J4") (pin "B5") (pinfunction "CC2_B5") (pintype "passive"))
      (node (ref "R15") (pin "1") (pinfunction "1_1") (pintype "passive"))
    )
    (net (code "73") (name "Net-(Q1-B)") (class "Default")
      (node (ref "Q1") (pin "1") (pinfunction "B_1") (pintype "passive"))
      (node (ref "R20") (pin "2") (pinfunction "2_2") (pintype "passive"))
    )
    (net (code "74") (name "Net-(Q2-B)") (class "Default")
      (node (ref "Q2") (pin "1") (pinfunction "B_1") (pintype "passive"))
      (node (ref "R26") (pin "2") (pinfunction "2_2") (pintype "passive"))
    )
    (net (code "75") (name "Net-(U2-CBUS0)") (class "Default")
      (node (ref "R7") (pin "1") (pinfunction "1_1") (pintype "passive"))
      (node (ref "U2") (pin "15") (pinfunction "CBUS0_15") (pintype "passive"))
    )
    (net (code "76") (name "unconnected-(J1-Pad24)") (class "Default")
      (node (ref "J1") (pin "24") (pinfunction "24_24") (pintype "passive+no_connect"))
    )
    (net (code "77") (name "unconnected-(J3-SBU1-PadA8)") (class "Default")
      (node (ref "J3") (pin "A8") (pinfunction "SBU1_A8") (pintype "passive"))
    )
    (net (code "78") (name "unconnected-(J3-SBU2-PadB8)") (class "Default")
      (node (ref "J3") (pin "B8") (pinfunction "SBU2_B8") (pintype "passive"))
    )
    (net (code "79") (name "unconnected-(J4-SBU1-PadA8)") (class "Default")
      (node (ref "J4") (pin "A8") (pinfunction "SBU1_A8") (pintype "passive"))
    )
    (net (code "80") (name "unconnected-(J4-SBU2-PadB8)") (class "Default")
      (node (ref "J4") (pin "B8") (pinfunction "SBU2_B8") (pintype "passive"))
    )
    (net (code "81") (name "unconnected-(U2-CBUS1-Pad14)") (class "Default")
      (node (ref "U2") (pin "14") (pinfunction "CBUS1_14") (pintype "passive+no_connect"))
    )
    (net (code "82") (name "unconnected-(U2-CBUS2-Pad7)") (class "Default")
      (node (ref "U2") (pin "7") (pinfunction "CBUS2_7") (pintype "passive+no_connect"))
    )
    (net (code "83") (name "unconnected-(U2-~{CTS}-Pad6)") (class "Default")
      (node (ref "U2") (pin "6") (pinfunction "~{CTS}_6") (pintype "passive+no_connect"))
    )
    (net (code "84") (name "unconnected-(U2-~{DCD}-Pad5)") (class "Default")
      (node (ref "U2") (pin "5") (pinfunction "~{DCD}_5") (pintype "passive+no_connect"))
    )
    (net (code "85") (name "unconnected-(U2-~{DSR}-Pad4)") (class "Default")
      (node (ref "U2") (pin "4") (pinfunction "~{DSR}_4") (pintype "passive+no_connect"))
    )
    (net (code "86") (name "unconnected-(U2-~{RI}-Pad2)") (class "Default")
      (node (ref "U2") (pin "2") (pinfunction "~{RI}_2") (pintype "passive+no_connect"))
    )
  )
)
